# CCM_0009.net
KiCad netlist of a schematic drawn in EAGLE
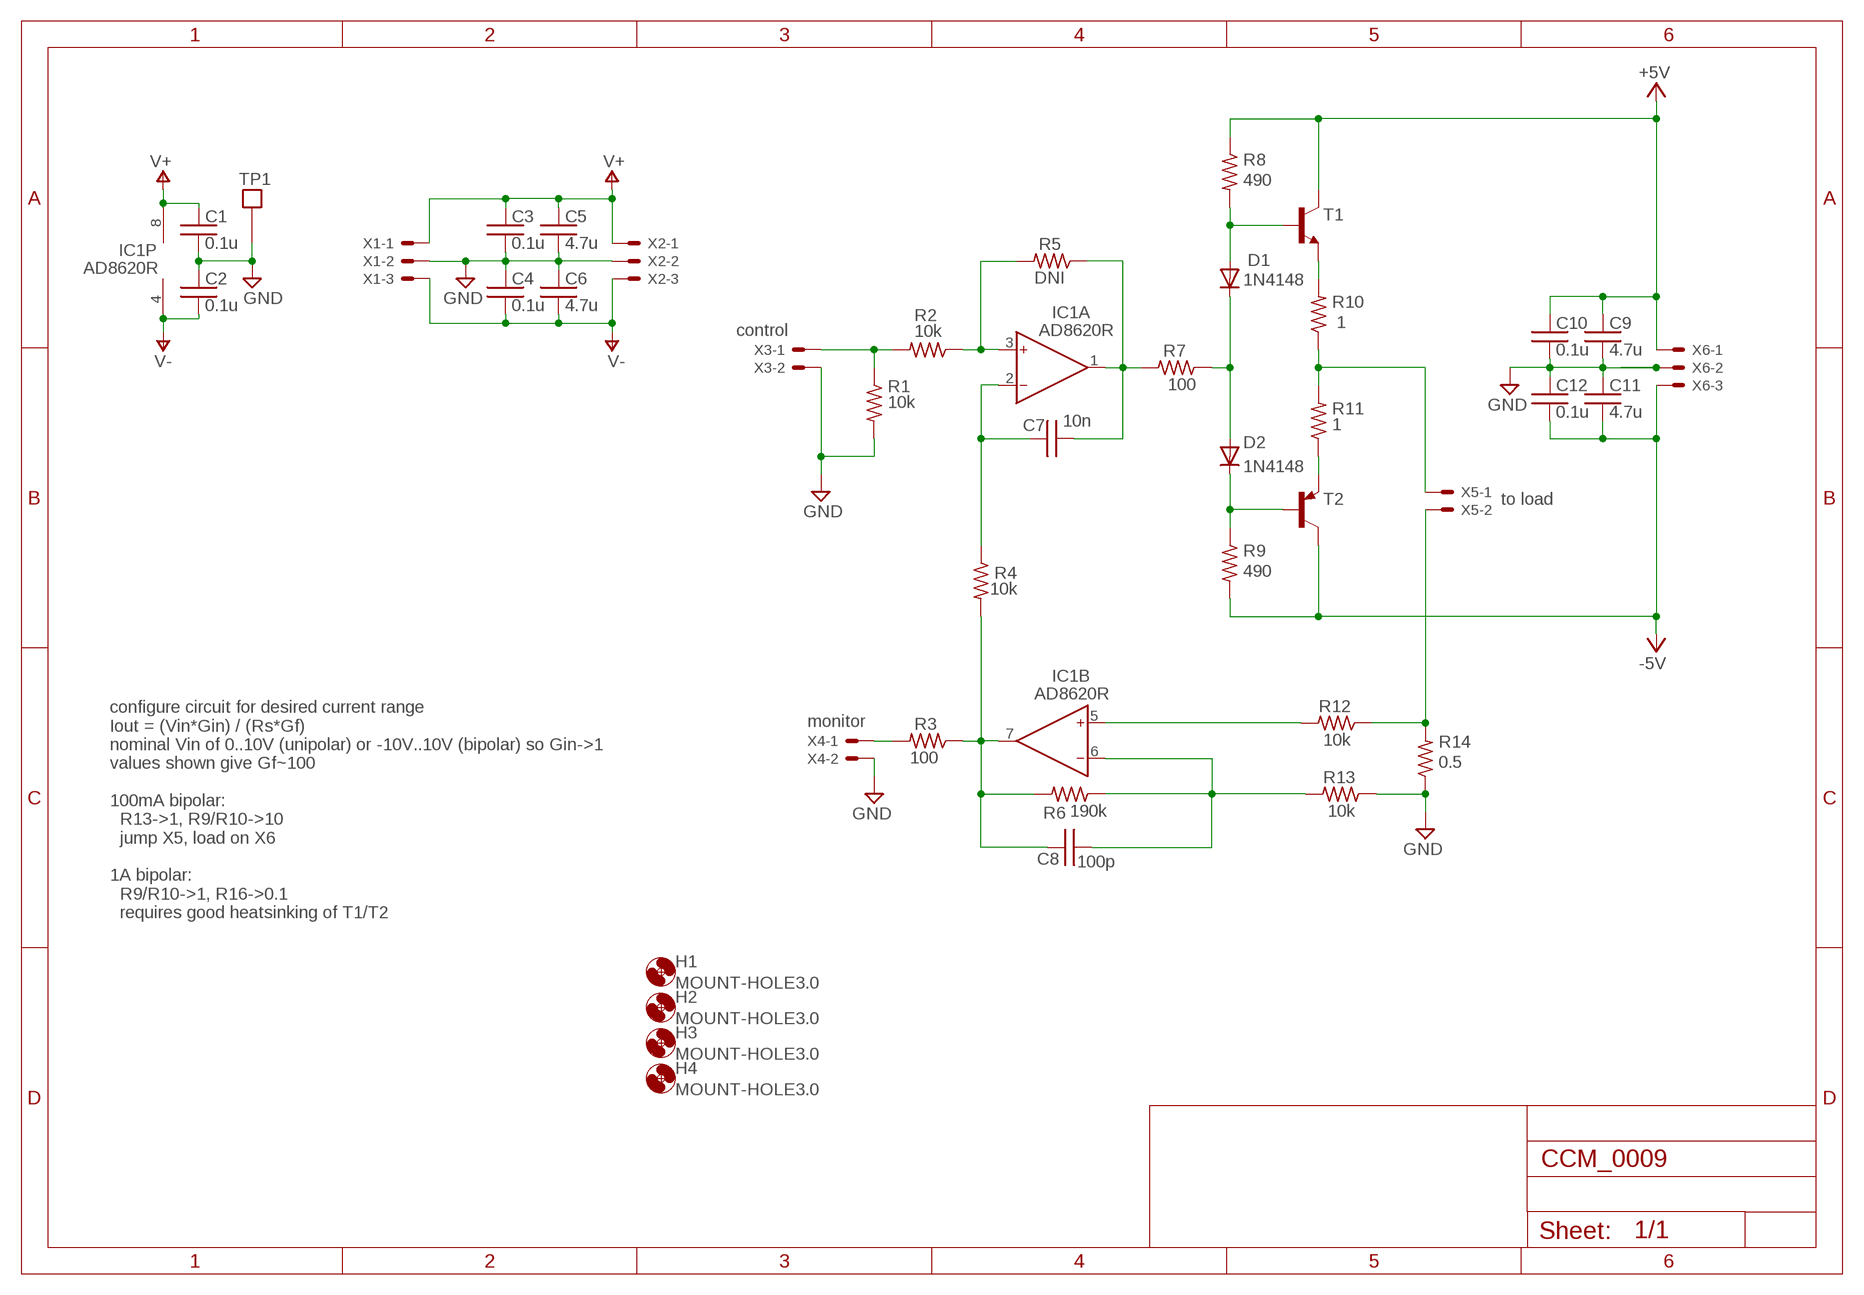
[diagram p0: schematic, sheet 1]

(export (version "E")
  (design (tool "Eeschema 10.0.6"))
  (components
    (comp (ref "C1")
      (value "0.1u")
      (footprint "eagle-import:0603")
      (libsource (lib "eagle-import") (part "C0603"))
    )
    (comp (ref "C2")
      (value "0.1u")
      (footprint "eagle-import:0603")
      (libsource (lib "eagle-import") (part "C0603"))
    )
    (comp (ref "C3")
      (value "0.1u")
      (footprint "eagle-import:0603")
      (libsource (lib "eagle-import") (part "C0603"))
    )
    (comp (ref "C4")
      (value "0.1u")
      (footprint "eagle-import:0603")
      (libsource (lib "eagle-import") (part "C0603"))
    )
    (comp (ref "C5")
      (value "4.7u")
      (footprint "eagle-import:0603")
      (libsource (lib "eagle-import") (part "C0603"))
    )
    (comp (ref "C6")
      (value "4.7u")
      (footprint "eagle-import:0603")
      (libsource (lib "eagle-import") (part "C0603"))
    )
    (comp (ref "C7")
      (value "10n")
      (footprint "eagle-import:0603")
      (libsource (lib "eagle-import") (part "C0603"))
    )
    (comp (ref "C8")
      (value "100p")
      (footprint "eagle-import:0603")
      (libsource (lib "eagle-import") (part "C0603"))
    )
    (comp (ref "C9")
      (value "4.7u")
      (footprint "eagle-import:0603")
      (libsource (lib "eagle-import") (part "C0603"))
    )
    (comp (ref "C10")
      (value "0.1u")
      (footprint "eagle-import:0603")
      (libsource (lib "eagle-import") (part "C0603"))
    )
    (comp (ref "C11")
      (value "4.7u")
      (footprint "eagle-import:0603")
      (libsource (lib "eagle-import") (part "C0603"))
    )
    (comp (ref "C12")
      (value "0.1u")
      (footprint "eagle-import:0603")
      (libsource (lib "eagle-import") (part "C0603"))
    )
    (comp (ref "D1")
      (value "1N4148")
      (footprint "eagle-import:SOD323_ST")
      (libsource (lib "eagle-import") (part "1N4148"))
    )
    (comp (ref "D2")
      (value "1N4148")
      (footprint "eagle-import:SOD323_ST")
      (libsource (lib "eagle-import") (part "1N4148"))
    )
    (comp (ref "H1")
      (value "MOUNT-HOLE3.0")
      (footprint "eagle-import:3,0")
      (libsource (lib "eagle-import") (part "MOUNT-HOLE3.0"))
    )
    (comp (ref "H2")
      (value "MOUNT-HOLE3.0")
      (footprint "eagle-import:3,0")
      (libsource (lib "eagle-import") (part "MOUNT-HOLE3.0"))
    )
    (comp (ref "H3")
      (value "MOUNT-HOLE3.0")
      (footprint "eagle-import:3,0")
      (libsource (lib "eagle-import") (part "MOUNT-HOLE3.0"))
    )
    (comp (ref "H4")
      (value "MOUNT-HOLE3.0")
      (footprint "eagle-import:3,0")
      (libsource (lib "eagle-import") (part "MOUNT-HOLE3.0"))
    )
    (comp (ref "IC1")
      (value "AD8620R")
      (footprint "eagle-import:SO8")
      (fields (field (name "MF") "ALTERA CORPORATION") (field (name "MPN") "AD8620ARZ"))
      (libsource (lib "eagle-import") (part "AD8620R"))
    )
    (comp (ref "R1")
      (value "10k")
      (footprint "eagle-import:0603")
      (libsource (lib "eagle-import") (part "R0603"))
    )
    (comp (ref "R2")
      (value "10k")
      (footprint "eagle-import:0603")
      (libsource (lib "eagle-import") (part "R0603"))
    )
    (comp (ref "R3")
      (value "100")
      (footprint "eagle-import:0603")
      (libsource (lib "eagle-import") (part "R0603"))
    )
    (comp (ref "R4")
      (value "10k")
      (footprint "eagle-import:0603")
      (libsource (lib "eagle-import") (part "R0603"))
    )
    (comp (ref "R5")
      (value "DNI")
      (footprint "eagle-import:0603")
      (libsource (lib "eagle-import") (part "R0603"))
    )
    (comp (ref "R6")
      (value "190k")
      (footprint "eagle-import:0603")
      (libsource (lib "eagle-import") (part "R0603"))
    )
    (comp (ref "R7")
      (value "100")
      (footprint "eagle-import:0603")
      (libsource (lib "eagle-import") (part "R0603"))
    )
    (comp (ref "R8")
      (value "490")
      (footprint "eagle-import:0603")
      (libsource (lib "eagle-import") (part "R0603"))
    )
    (comp (ref "R9")
      (value "490")
      (footprint "eagle-import:0603")
      (libsource (lib "eagle-import") (part "R0603"))
    )
    (comp (ref "R10")
      (value "1")
      (footprint "eagle-import:LTO30")
      (libsource (lib "eagle-import") (part "LT030"))
    )
    (comp (ref "R11")
      (value "1")
      (footprint "eagle-import:LTO30")
      (libsource (lib "eagle-import") (part "LT030"))
    )
    (comp (ref "R12")
      (value "10k")
      (footprint "eagle-import:0603")
      (libsource (lib "eagle-import") (part "R0603"))
    )
    (comp (ref "R13")
      (value "10k")
      (footprint "eagle-import:0603")
      (libsource (lib "eagle-import") (part "R0603"))
    )
    (comp (ref "R14")
      (value "0.5")
      (footprint "eagle-import:LTO30")
      (libsource (lib "eagle-import") (part "LT030"))
    )
    (comp (ref "T1")
      (value "TIP29")
      (footprint "eagle-import:TO220V")
      (libsource (lib "eagle-import") (part "-NPN-TO220V"))
    )
    (comp (ref "T2")
      (value "TIP30")
      (footprint "eagle-import:TO220V")
      (libsource (lib "eagle-import") (part "-PNP-TO220V"))
    )
    (comp (ref "TP1")
      (value "TESTPOINT")
      (footprint "eagle-import:TESTPOINT")
      (libsource (lib "eagle-import") (part "TESTPOINT"))
    )
    (comp (ref "X1")
      (value "22-23-2031")
      (footprint "eagle-import:22-23-2031")
      (fields (field (name "MF") "MOLEX"))
      (libsource (lib "eagle-import") (part "22-23-2031"))
    )
    (comp (ref "X2")
      (value "22-23-2031")
      (footprint "eagle-import:22-23-2031")
      (fields (field (name "MF") "MOLEX"))
      (libsource (lib "eagle-import") (part "22-23-2031"))
    )
    (comp (ref "X3")
      (value "22-23-2021")
      (footprint "eagle-import:22-23-2021")
      (fields (field (name "MF") "MOLEX"))
      (libsource (lib "eagle-import") (part "22-23-2021"))
    )
    (comp (ref "X4")
      (value "22-23-2021")
      (footprint "eagle-import:22-23-2021")
      (fields (field (name "MF") "MOLEX"))
      (libsource (lib "eagle-import") (part "22-23-2021"))
    )
    (comp (ref "X5")
      (value "22-23-2021")
      (footprint "eagle-import:22-23-2021")
      (fields (field (name "MF") "MOLEX"))
      (libsource (lib "eagle-import") (part "22-23-2021"))
    )
    (comp (ref "X6")
      (value "22-23-2031")
      (footprint "eagle-import:22-23-2031")
      (fields (field (name "MF") "MOLEX"))
      (libsource (lib "eagle-import") (part "con-molex_165_22-23-2031"))
    )
  )
  (nets
    (net (code "1") (name "+5V") (class "Default")
      (node (ref "C10") (pin "1") (pinfunction "1_1") (pintype "passive"))
      (node (ref "C9") (pin "1") (pinfunction "1_1") (pintype "passive"))
      (node (ref "R8") (pin "1") (pinfunction "1_1") (pintype "passive"))
      (node (ref "T1") (pin "2") (pinfunction "C_2") (pintype "passive"))
      (node (ref "X6") (pin "1") (pinfunction "S_1") (pintype "passive"))
    )
    (net (code "2") (name "-5V") (class "Default")
      (node (ref "C11") (pin "2") (pinfunction "2_2") (pintype "passive"))
      (node (ref "C12") (pin "2") (pinfunction "2_2") (pintype "passive"))
      (node (ref "R9") (pin "2") (pinfunction "2_2") (pintype "passive"))
      (node (ref "T2") (pin "2") (pinfunction "C_2") (pintype "passive"))
      (node (ref "X6") (pin "3") (pinfunction "S_3") (pintype "passive"))
    )
    (net (code "3") (name "GND") (class "Default")
      (node (ref "C1") (pin "2") (pinfunction "2_2") (pintype "passive"))
      (node (ref "C10") (pin "2") (pinfunction "2_2") (pintype "passive"))
      (node (ref "C11") (pin "1") (pinfunction "1_1") (pintype "passive"))
      (node (ref "C12") (pin "1") (pinfunction "1_1") (pintype "passive"))
      (node (ref "C2") (pin "1") (pinfunction "1_1") (pintype "passive"))
      (node (ref "C3") (pin "2") (pinfunction "2_2") (pintype "passive"))
      (node (ref "C4") (pin "1") (pinfunction "1_1") (pintype "passive"))
      (node (ref "C5") (pin "2") (pinfunction "2_2") (pintype "passive"))
      (node (ref "C6") (pin "1") (pinfunction "1_1") (pintype "passive"))
      (node (ref "C9") (pin "2") (pinfunction "2_2") (pintype "passive"))
      (node (ref "R1") (pin "2") (pinfunction "2_2") (pintype "passive"))
      (node (ref "R13") (pin "1") (pinfunction "1_1") (pintype "passive"))
      (node (ref "R14") (pin "P$1") (pinfunction "1_P$1") (pintype "passive"))
      (node (ref "TP1") (pin "P$1") (pinfunction "P$1_P$1") (pintype "bidirectional"))
      (node (ref "X1") (pin "2") (pinfunction "S_2") (pintype "passive"))
      (node (ref "X2") (pin "2") (pinfunction "S_2") (pintype "passive"))
      (node (ref "X3") (pin "2") (pinfunction "S_2") (pintype "passive"))
      (node (ref "X4") (pin "2") (pinfunction "S_2") (pintype "passive"))
      (node (ref "X6") (pin "2") (pinfunction "S_2") (pintype "passive"))
    )
    (net (code "4") (name "Net-(D1-PadC)") (class "Default")
      (node (ref "D1") (pin "C") (pinfunction "C_C") (pintype "passive"))
      (node (ref "D2") (pin "A") (pinfunction "A_A") (pintype "passive"))
      (node (ref "R7") (pin "1") (pinfunction "1_1") (pintype "passive"))
    )
    (net (code "5") (name "Net-(IC1A-IN+)") (class "Default")
      (node (ref "IC1") (pin "3") (pinfunction "IN+_3") (pintype "input"))
      (node (ref "R2") (pin "1") (pinfunction "1_1") (pintype "passive"))
      (node (ref "R5") (pin "2") (pinfunction "2_2") (pintype "passive"))
    )
    (net (code "6") (name "Net-(IC1A-IN-)") (class "Default")
      (node (ref "C7") (pin "1") (pinfunction "1_1") (pintype "passive"))
      (node (ref "IC1") (pin "2") (pinfunction "IN-_2") (pintype "input"))
      (node (ref "R4") (pin "1") (pinfunction "1_1") (pintype "passive"))
    )
    (net (code "7") (name "Net-(IC1A-OUT)") (class "Default")
      (node (ref "C7") (pin "2") (pinfunction "2_2") (pintype "passive"))
      (node (ref "IC1") (pin "1") (pinfunction "OUT_1") (pintype "output"))
      (node (ref "R5") (pin "1") (pinfunction "1_1") (pintype "passive"))
      (node (ref "R7") (pin "2") (pinfunction "2_2") (pintype "passive"))
    )
    (net (code "8") (name "Net-(IC1B-IN+)") (class "Default")
      (node (ref "IC1") (pin "5") (pinfunction "IN+_5") (pintype "input"))
      (node (ref "R12") (pin "2") (pinfunction "2_2") (pintype "passive"))
    )
    (net (code "9") (name "Net-(IC1B-IN-)") (class "Default")
      (node (ref "C8") (pin "2") (pinfunction "2_2") (pintype "passive"))
      (node (ref "IC1") (pin "6") (pinfunction "IN-_6") (pintype "input"))
      (node (ref "R13") (pin "2") (pinfunction "2_2") (pintype "passive"))
      (node (ref "R6") (pin "1") (pinfunction "1_1") (pintype "passive"))
    )
    (net (code "10") (name "Net-(IC1B-OUT)") (class "Default")
      (node (ref "C8") (pin "1") (pinfunction "1_1") (pintype "passive"))
      (node (ref "IC1") (pin "7") (pinfunction "OUT_7") (pintype "output"))
      (node (ref "R3") (pin "1") (pinfunction "1_1") (pintype "passive"))
      (node (ref "R4") (pin "2") (pinfunction "2_2") (pintype "passive"))
      (node (ref "R6") (pin "2") (pinfunction "2_2") (pintype "passive"))
    )
    (net (code "11") (name "Net-(R10-1)") (class "Default")
      (node (ref "R10") (pin "P$1") (pinfunction "1_P$1") (pintype "passive"))
      (node (ref "R11") (pin "P$2") (pinfunction "2_P$2") (pintype "passive"))
      (node (ref "X5") (pin "1") (pinfunction "S_1") (pintype "passive"))
    )
    (net (code "12") (name "Net-(R10-2)") (class "Default")
      (node (ref "R10") (pin "P$2") (pinfunction "2_P$2") (pintype "passive"))
      (node (ref "T1") (pin "3") (pinfunction "E_3") (pintype "passive"))
    )
    (net (code "13") (name "Net-(R11-1)") (class "Default")
      (node (ref "R11") (pin "P$1") (pinfunction "1_P$1") (pintype "passive"))
      (node (ref "T2") (pin "3") (pinfunction "E_3") (pintype "passive"))
    )
    (net (code "14") (name "Net-(R14-2)") (class "Default")
      (node (ref "R12") (pin "1") (pinfunction "1_1") (pintype "passive"))
      (node (ref "R14") (pin "P$2") (pinfunction "2_P$2") (pintype "passive"))
      (node (ref "X5") (pin "2") (pinfunction "S_2") (pintype "passive"))
    )
    (net (code "15") (name "Net-(T1-B)") (class "Default")
      (node (ref "D1") (pin "A") (pinfunction "A_A") (pintype "passive"))
      (node (ref "R8") (pin "2") (pinfunction "2_2") (pintype "passive"))
      (node (ref "T1") (pin "1") (pinfunction "B_1") (pintype "passive"))
    )
    (net (code "16") (name "Net-(T2-B)") (class "Default")
      (node (ref "D2") (pin "C") (pinfunction "C_C") (pintype "passive"))
      (node (ref "R9") (pin "1") (pinfunction "1_1") (pintype "passive"))
      (node (ref "T2") (pin "1") (pinfunction "B_1") (pintype "passive"))
    )
    (net (code "17") (name "Net-(X3A-S)") (class "Default")
      (node (ref "R1") (pin "1") (pinfunction "1_1") (pintype "passive"))
      (node (ref "R2") (pin "2") (pinfunction "2_2") (pintype "passive"))
      (node (ref "X3") (pin "1") (pinfunction "S_1") (pintype "passive"))
    )
    (net (code "18") (name "Net-(X4A-S)") (class "Default")
      (node (ref "R3") (pin "2") (pinfunction "2_2") (pintype "passive"))
      (node (ref "X4") (pin "1") (pinfunction "S_1") (pintype "passive"))
    )
    (net (code "19") (name "V+") (class "Default")
      (node (ref "C1") (pin "1") (pinfunction "1_1") (pintype "passive"))
      (node (ref "C3") (pin "1") (pinfunction "1_1") (pintype "passive"))
      (node (ref "C5") (pin "1") (pinfunction "1_1") (pintype "passive"))
      (node (ref "IC1") (pin "8") (pinfunction "V+_8") (pintype "power_in"))
      (node (ref "X1") (pin "1") (pinfunction "S_1") (pintype "passive"))
      (node (ref "X2") (pin "1") (pinfunction "S_1") (pintype "passive"))
    )
    (net (code "20") (name "V-") (class "Default")
      (node (ref "C2") (pin "2") (pinfunction "2_2") (pintype "passive"))
      (node (ref "C4") (pin "2") (pinfunction "2_2") (pintype "passive"))
      (node (ref "C6") (pin "2") (pinfunction "2_2") (pintype "passive"))
      (node (ref "IC1") (pin "4") (pinfunction "V-_4") (pintype "power_in"))
      (node (ref "X1") (pin "3") (pinfunction "S_3") (pintype "passive"))
      (node (ref "X2") (pin "3") (pinfunction "S_3") (pintype "passive"))
    )
  )
)
